# p2_eth_rs232.net
KiCad netlist of a schematic drawn in Altium Designer
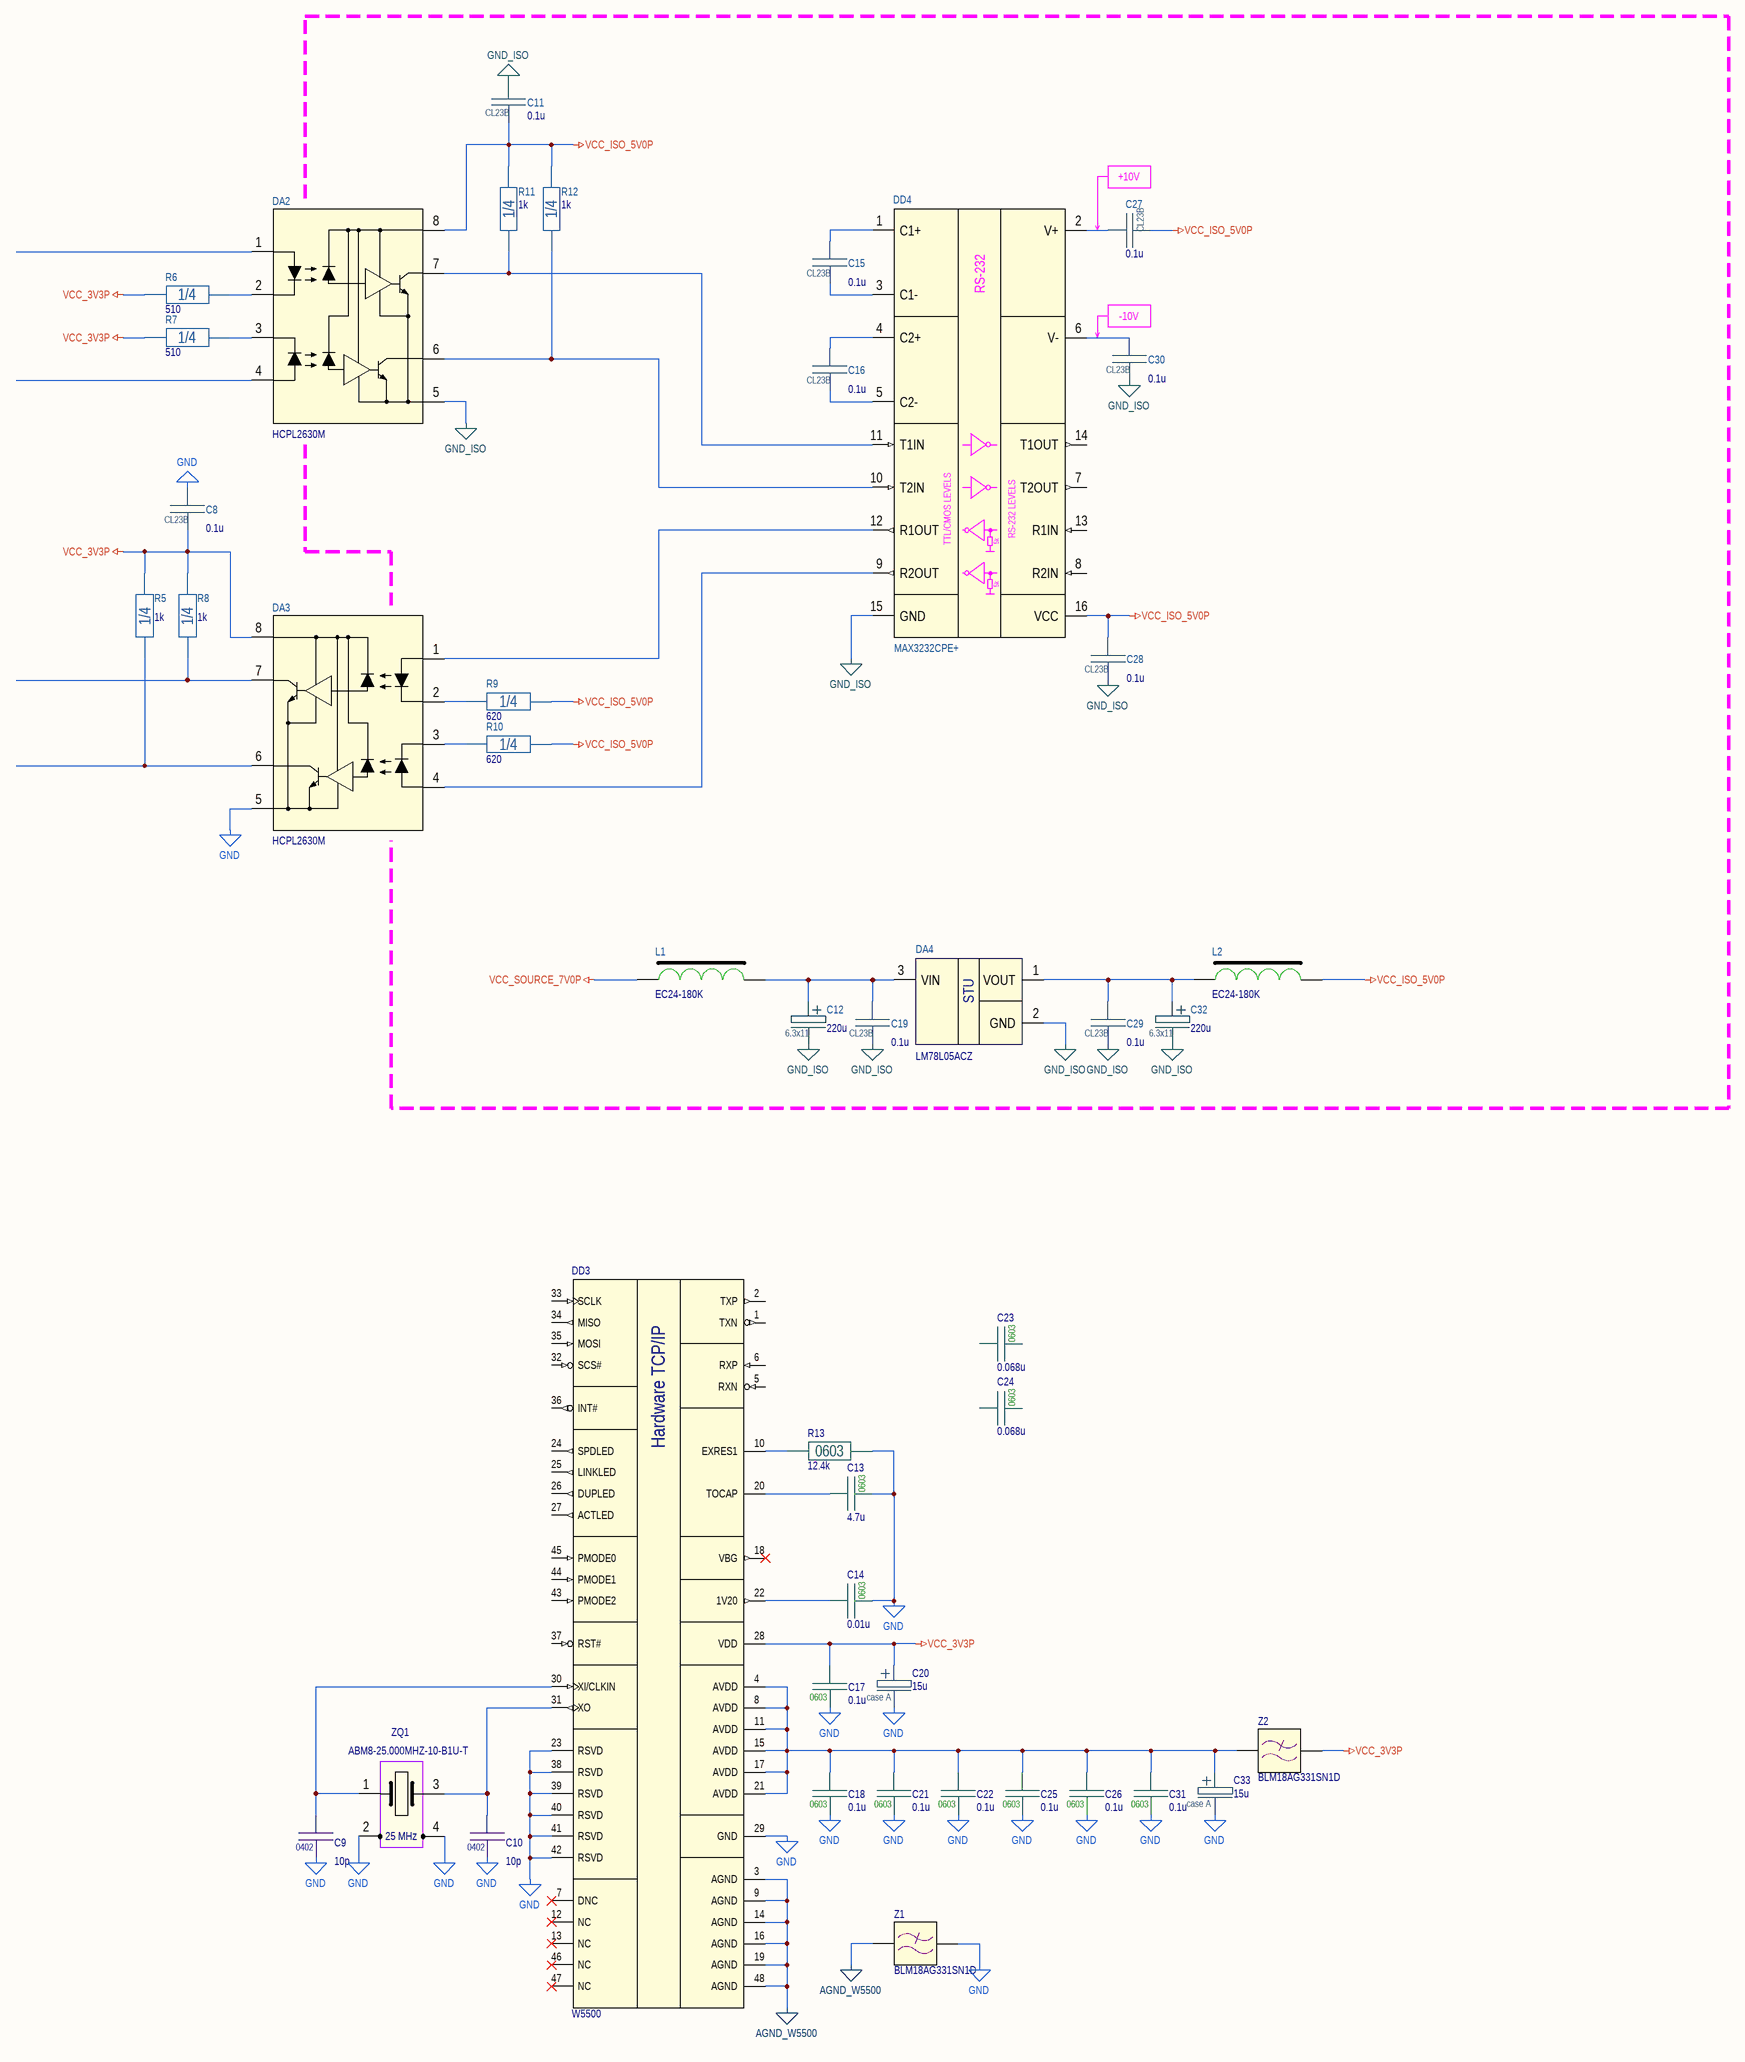
[diagram p0: p2_eth_rs232.SchDoc]

(export (version "E")
  (design (tool "Eeschema 10.0.6"))
  (components
    (comp (ref "C8")
      (value "0.1u")
      (footprint "PcbLib_RC:CL23B_7.2x2.5")
      (description "Box-type metallized polyester film capacitor")
      (fields
        (field (name "TOLERANCE") "± * %")
        (field (name "VOLTAGE") "63V")
        (field (name "PACKAGE") "CL23B")
      )
      (libsource (lib "Schlib_RC") (part "CL23B"))
    )
    (comp (ref "C9")
      (value "10p")
      (footprint "PcbLib_RC:CAP0402")
      (description "Capacitors 0402 package case")
      (fields
        (field (name "TOLERANCE") "± 10 %")
        (field (name "VOLTAGE") "50 V")
        (field (name "PACKAGE") "0402")
      )
      (libsource (lib "Schlib_RC") (part "C0402"))
    )
    (comp (ref "C10")
      (value "10p")
      (footprint "PcbLib_RC:CAP0402")
      (description "Capacitors 0402 package case")
      (fields
        (field (name "TOLERANCE") "± 10 %")
        (field (name "VOLTAGE") "50 V")
        (field (name "PACKAGE") "0402")
      )
      (libsource (lib "Schlib_RC") (part "C0402"))
    )
    (comp (ref "C11")
      (value "0.1u")
      (footprint "PcbLib_RC:CL23B_7.2x2.5")
      (description "Box-type metallized polyester film capacitor")
      (fields
        (field (name "TOLERANCE") "± * %")
        (field (name "VOLTAGE") "63V")
        (field (name "PACKAGE") "CL23B")
      )
      (libsource (lib "Schlib_RC") (part "CL23B"))
    )
    (comp (ref "C12")
      (value "220u")
      (footprint "PcbLib_RC:ECAP6.3X11X2.5_BRW")
      (description "Aluminium capacitor")
      (fields
        (field (name "TOLERANCE") "± 20 %")
        (field (name "VOLTAGE") "16V")
        (field (name "PACKAGE") "6.3x11")
      )
      (libsource (lib "Schlib_RC") (part "C_ECAP"))
    )
    (comp (ref "C13")
      (value "4.7u")
      (footprint "PcbLib_RC:CAP0603")
      (description "Capacitors 0603 package case")
      (fields
        (field (name "TOLERANCE") "± 10 %")
        (field (name "VOLTAGE") "16 V")
        (field (name "PACKAGE") "0603")
      )
      (libsource (lib "Schlib_RC") (part "C0603"))
    )
    (comp (ref "C14")
      (value "0.01u")
      (footprint "PcbLib_RC:CAP0603")
      (description "Capacitors 0603 package case")
      (fields
        (field (name "TOLERANCE") "± 10 %")
        (field (name "VOLTAGE") "50 V")
        (field (name "PACKAGE") "0603")
      )
      (libsource (lib "Schlib_RC") (part "C0603"))
    )
    (comp (ref "C15")
      (value "0.1u")
      (footprint "PcbLib_RC:CL23B_7.2x2.5")
      (description "Box-type metallized polyester film capacitor")
      (fields
        (field (name "TOLERANCE") "± * %")
        (field (name "VOLTAGE") "63V")
        (field (name "PACKAGE") "CL23B")
      )
      (libsource (lib "Schlib_RC") (part "CL23B"))
    )
    (comp (ref "C16")
      (value "0.1u")
      (footprint "PcbLib_RC:CL23B_7.2x2.5")
      (description "Box-type metallized polyester film capacitor")
      (fields
        (field (name "TOLERANCE") "± * %")
        (field (name "VOLTAGE") "63V")
        (field (name "PACKAGE") "CL23B")
      )
      (libsource (lib "Schlib_RC") (part "CL23B"))
    )
    (comp (ref "C17")
      (value "0.1u")
      (footprint "PcbLib_RC:CAP0603")
      (description "Capacitors 0603 package case")
      (fields
        (field (name "TOLERANCE") "± 10 %")
        (field (name "VOLTAGE") "50V")
        (field (name "PACKAGE") "0603")
      )
      (libsource (lib "Schlib_RC") (part "C0603"))
    )
    (comp (ref "C18")
      (value "0.1u")
      (footprint "PcbLib_RC:CAP0603")
      (description "Capacitors 0603 package case")
      (fields
        (field (name "TOLERANCE") "± 10 %")
        (field (name "VOLTAGE") "50V")
        (field (name "PACKAGE") "0603")
      )
      (libsource (lib "Schlib_RC") (part "C0603"))
    )
    (comp (ref "C19")
      (value "0.1u")
      (footprint "PcbLib_RC:CL23B_7.2x2.5")
      (description "Box-type metallized polyester film capacitor")
      (fields
        (field (name "TOLERANCE") "± * %")
        (field (name "VOLTAGE") "63V")
        (field (name "PACKAGE") "CL23B")
      )
      (libsource (lib "Schlib_RC") (part "CL23B"))
    )
    (comp (ref "C20")
      (value "15u")
      (footprint "PcbLib_RC:CAP_CASE_A")
      (description "Tantalum capacitors case A")
      (fields
        (field (name "TOLERANCE") "± 10 %")
        (field (name "VOLTAGE") "6.3V")
        (field (name "PACKAGE") "case A")
      )
      (libsource (lib "Schlib_RC") (part "C_CASEA"))
    )
    (comp (ref "C21")
      (value "0.1u")
      (footprint "PcbLib_RC:CAP0603")
      (description "Capacitors 0603 package case")
      (fields
        (field (name "TOLERANCE") "± 10 %")
        (field (name "VOLTAGE") "50V")
        (field (name "PACKAGE") "0603")
      )
      (libsource (lib "Schlib_RC") (part "C0603"))
    )
    (comp (ref "C22")
      (value "0.1u")
      (footprint "PcbLib_RC:CAP0603")
      (description "Capacitors 0603 package case")
      (fields
        (field (name "TOLERANCE") "± 10 %")
        (field (name "VOLTAGE") "50V")
        (field (name "PACKAGE") "0603")
      )
      (libsource (lib "Schlib_RC") (part "C0603"))
    )
    (comp (ref "C23")
      (value "0.068u")
      (footprint "PcbLib_RC:CAP0603")
      (description "Capacitors 0603 package case")
      (fields
        (field (name "TOLERANCE") "± 10 %")
        (field (name "VOLTAGE") "50 V")
        (field (name "PACKAGE") "0603")
      )
      (libsource (lib "Schlib_RC") (part "C0603"))
    )
    (comp (ref "C24")
      (value "0.068u")
      (footprint "PcbLib_RC:CAP0603")
      (description "Capacitors 0603 package case")
      (fields
        (field (name "TOLERANCE") "± 10 %")
        (field (name "VOLTAGE") "50 V")
        (field (name "PACKAGE") "0603")
      )
      (libsource (lib "Schlib_RC") (part "C0603"))
    )
    (comp (ref "C25")
      (value "0.1u")
      (footprint "PcbLib_RC:CAP0603")
      (description "Capacitors 0603 package case")
      (fields
        (field (name "TOLERANCE") "± 10 %")
        (field (name "VOLTAGE") "50V")
        (field (name "PACKAGE") "0603")
      )
      (libsource (lib "Schlib_RC") (part "C0603"))
    )
    (comp (ref "C26")
      (value "0.1u")
      (footprint "PcbLib_RC:CAP0603")
      (description "Capacitors 0603 package case")
      (fields
        (field (name "TOLERANCE") "± 10 %")
        (field (name "VOLTAGE") "50V")
        (field (name "PACKAGE") "0603")
      )
      (libsource (lib "Schlib_RC") (part "C0603"))
    )
    (comp (ref "C27")
      (value "0.1u")
      (footprint "PcbLib_RC:CL23B_7.2x2.5")
      (description "Box-type metallized polyester film capacitor")
      (fields
        (field (name "TOLERANCE") "± * %")
        (field (name "VOLTAGE") "63V")
        (field (name "PACKAGE") "CL23B")
      )
      (libsource (lib "Schlib_RC") (part "CL23B"))
    )
    (comp (ref "C28")
      (value "0.1u")
      (footprint "PcbLib_RC:CL23B_7.2x2.5")
      (description "Box-type metallized polyester film capacitor")
      (fields
        (field (name "TOLERANCE") "± * %")
        (field (name "VOLTAGE") "63V")
        (field (name "PACKAGE") "CL23B")
      )
      (libsource (lib "Schlib_RC") (part "CL23B"))
    )
    (comp (ref "C29")
      (value "0.1u")
      (footprint "PcbLib_RC:CL23B_7.2x2.5")
      (description "Box-type metallized polyester film capacitor")
      (fields
        (field (name "TOLERANCE") "± * %")
        (field (name "VOLTAGE") "63V")
        (field (name "PACKAGE") "CL23B")
      )
      (libsource (lib "Schlib_RC") (part "CL23B"))
    )
    (comp (ref "C30")
      (value "0.1u")
      (footprint "PcbLib_RC:CL23B_7.2x2.5")
      (description "Box-type metallized polyester film capacitor")
      (fields
        (field (name "TOLERANCE") "± * %")
        (field (name "VOLTAGE") "63V")
        (field (name "PACKAGE") "CL23B")
      )
      (libsource (lib "Schlib_RC") (part "CL23B"))
    )
    (comp (ref "C31")
      (value "0.1u")
      (footprint "PcbLib_RC:CAP0603")
      (description "Capacitors 0603 package case")
      (fields
        (field (name "TOLERANCE") "± 10 %")
        (field (name "VOLTAGE") "50V")
        (field (name "PACKAGE") "0603")
      )
      (libsource (lib "Schlib_RC") (part "C0603"))
    )
    (comp (ref "C32")
      (value "220u")
      (footprint "PcbLib_RC:ECAP6.3X11X2.5_BRW")
      (description "Aluminium capacitor")
      (fields
        (field (name "TOLERANCE") "± 20 %")
        (field (name "VOLTAGE") "16V")
        (field (name "PACKAGE") "6.3x11")
      )
      (libsource (lib "Schlib_RC") (part "C_ECAP"))
    )
    (comp (ref "C33")
      (value "15u")
      (footprint "PcbLib_RC:CAP_CASE_A")
      (description "Tantalum capacitors case A")
      (fields
        (field (name "TOLERANCE") "± 10 %")
        (field (name "VOLTAGE") "6.3V")
        (field (name "PACKAGE") "case A")
      )
      (libsource (lib "Schlib_RC") (part "C_CASEA"))
    )
    (comp (ref "DA2")
      (value "HCPL2630M")
      (footprint "PcbLib_ICs:DIP-8P-M01")
      (description "Dual-Channel High-Speed 10 MBit/s Logic Gate Optocouplers")
      (fields (field (name "MANUFACTURER") "ON Semiconductor"))
      (libsource (lib "Schlib_ONSemiconductor") (part "HCPL2630M"))
    )
    (comp (ref "DA3")
      (value "HCPL2630M")
      (footprint "PcbLib_ICs:DIP-8P-M01")
      (description "Dual-Channel High-Speed 10 MBit/s Logic Gate Optocouplers")
      (fields (field (name "MANUFACTURER") "ON Semiconductor"))
      (libsource (lib "Schlib_ONSemiconductor") (part "HCPL2630M"))
    )
    (comp (ref "DA4")
      (value "LM78L05ACZ")
      (footprint "PcbLib_ICs:TO-92 (VERTICAL,LINE)")
      (description "100-mA Fixed Output Linear Regulator")
      (fields (field (name "MANUFACTURER") "Texas Instruments"))
      (libsource (lib "Schlib_Texas_Instruments") (part "LM78L05ACZ"))
    )
    (comp (ref "DD3")
      (value "W5500")
      (footprint "PcbLib_ICs:LQFP-48")
      (description "Hardwired TCP/IP embedded Ethernet controller")
      (fields (field (name "MANUFACTURER") "WIZnet"))
      (libsource (lib "Schlib_Wiznet") (part "W5500"))
    )
    (comp (ref "DD4")
      (value "MAX3232CPE+")
      (footprint "PcbLib_ICs:DIP-16P-M03")
      (description "3.0V to 5.5V, Low-Power, Up to 1Mbps, True RS-232 Transceivers")
      (fields (field (name "MANUFACTURER") "Maxim Integrated"))
      (libsource (lib "Schlib_Maxim_Integrated") (part "MAX3232CPE+"))
    )
    (comp (ref "L1")
      (value "EC24-180K")
      (footprint "PcbLib_RC:EC24_GREEN")
      (description "Axial leaded coated inductors")
      (fields (field (name "MANUFACTURER") "3L Electronic"))
      (libsource (lib "Schlib_RC") (part "EC24"))
    )
    (comp (ref "L2")
      (value "EC24-180K")
      (footprint "PcbLib_RC:EC24_GREEN")
      (description "Axial leaded coated inductors")
      (fields (field (name "MANUFACTURER") "3L Electronic"))
      (libsource (lib "Schlib_RC") (part "EC24"))
    )
    (comp (ref "R5")
      (value "1k")
      (footprint "PcbLib_RC:CFR-25")
      (description "Resistor 1/4W")
      (fields
        (field (name "TOLERANCE") "± 1 %")
        (field (name "PART NUMBER") "MFR-25FTF52-1K")
        (field (name "PACKAGE") "1/4")
      )
      (libsource (lib "Schlib_RC") (part "CF25"))
    )
    (comp (ref "R6")
      (value "510")
      (footprint "PcbLib_RC:CFR-25")
      (description "Resistor 1/4W")
      (fields
        (field (name "TOLERANCE") "± 1 %")
        (field (name "PART NUMBER") "MFR-25FTF52-510R")
        (field (name "PACKAGE") "1/4")
      )
      (libsource (lib "Schlib_RC") (part "CF25"))
    )
    (comp (ref "R7")
      (value "510")
      (footprint "PcbLib_RC:CFR-25")
      (description "Resistor 1/4W")
      (fields
        (field (name "TOLERANCE") "± 1 %")
        (field (name "PART NUMBER") "MFR-25FTF52-510R")
        (field (name "PACKAGE") "1/4")
      )
      (libsource (lib "Schlib_RC") (part "CF25"))
    )
    (comp (ref "R8")
      (value "1k")
      (footprint "PcbLib_RC:CFR-25")
      (description "Resistor 1/4W")
      (fields
        (field (name "TOLERANCE") "± 1 %")
        (field (name "PART NUMBER") "MFR-25FTF52-1K")
        (field (name "PACKAGE") "1/4")
      )
      (libsource (lib "Schlib_RC") (part "CF25"))
    )
    (comp (ref "R9")
      (value "620")
      (footprint "PcbLib_RC:CFR-25")
      (description "Resistor 1/4W")
      (fields
        (field (name "TOLERANCE") "± 1 %")
        (field (name "PART NUMBER") "MFR-25FTF52-620R")
        (field (name "PACKAGE") "1/4")
      )
      (libsource (lib "Schlib_RC") (part "CF25"))
    )
    (comp (ref "R10")
      (value "620")
      (footprint "PcbLib_RC:CFR-25")
      (description "Resistor 1/4W")
      (fields
        (field (name "TOLERANCE") "± 1 %")
        (field (name "PART NUMBER") "MFR-25FTF52-620R")
        (field (name "PACKAGE") "1/4")
      )
      (libsource (lib "Schlib_RC") (part "CF25"))
    )
    (comp (ref "R11")
      (value "1k")
      (footprint "PcbLib_RC:CFR-25")
      (description "Resistor 1/4W")
      (fields
        (field (name "TOLERANCE") "± 1 %")
        (field (name "PART NUMBER") "MFR-25FTF52-1K")
        (field (name "PACKAGE") "1/4")
      )
      (libsource (lib "Schlib_RC") (part "CF25"))
    )
    (comp (ref "R12")
      (value "1k")
      (footprint "PcbLib_RC:CFR-25")
      (description "Resistor 1/4W")
      (fields
        (field (name "TOLERANCE") "± 1 %")
        (field (name "PART NUMBER") "MFR-25FTF52-1K")
        (field (name "PACKAGE") "1/4")
      )
      (libsource (lib "Schlib_RC") (part "CF25"))
    )
    (comp (ref "R13")
      (value "12.4k")
      (footprint "PcbLib_RC:RES0603B")
      (description "Resistor 0603 package case")
      (fields
        (field (name "TOLERANCE") "± 1 %")
        (field (name "PART NUMBER") "RC0603FR-0712K4L")
        (field (name "PACKAGE") "0603")
      )
      (libsource (lib "Schlib_RC") (part "R0603"))
    )
    (comp (ref "Z1")
      (value "BLM18AG331SN1D")
      (footprint "PcbLib_RC:BLM0603P")
      (description "Power line filter, imperdance 330 Ohm (current 05A)")
      (libsource (lib "Schlib_Murata") (part "BLM18AG331SN1D"))
    )
    (comp (ref "Z2")
      (value "BLM18AG331SN1D")
      (footprint "PcbLib_RC:BLM0603P")
      (description "Power line filter, imperdance 330 Ohm (current 05A)")
      (libsource (lib "Schlib_Murata") (part "BLM18AG331SN1D"))
    )
    (comp (ref "ZQ1")
      (value "ABM8-25.000MHZ-10-B1U-T")
      (footprint "PcbLib_Others:SMD3225")
      (description "Quartz Crystal (Frequency Stability ±10ppm)")
      (fields (field (name "MANUFACTURER") "Abracon LLC"))
      (libsource (lib "Schlib_AbraconLLC") (part "ABM8-25.000MHZ-10-B1U-T"))
    )
  )
  (nets
    (net (code "1") (name "AGND_W5500") (class "Default")
      (node (ref "DD3") (pin "14") (pinfunction "AGND_14") (pintype "power_in"))
      (node (ref "DD3") (pin "16") (pinfunction "AGND_16") (pintype "power_in"))
      (node (ref "DD3") (pin "19") (pinfunction "AGND_19") (pintype "power_in"))
      (node (ref "DD3") (pin "3") (pinfunction "AGND_3") (pintype "power_in"))
      (node (ref "DD3") (pin "48") (pinfunction "AGND_48") (pintype "power_in"))
      (node (ref "DD3") (pin "9") (pinfunction "AGND_9") (pintype "power_in"))
      (node (ref "Z1") (pin "2") (pinfunction "2_2") (pintype "passive"))
    )
    (net (code "2") (name "GND") (class "Default")
      (node (ref "C10") (pin "1") (pinfunction "1_1") (pintype "passive"))
      (node (ref "C13") (pin "2") (pinfunction "2_2") (pintype "passive"))
      (node (ref "C14") (pin "2") (pinfunction "2_2") (pintype "passive"))
      (node (ref "C17") (pin "1") (pinfunction "1_1") (pintype "passive"))
      (node (ref "C18") (pin "1") (pinfunction "1_1") (pintype "passive"))
      (node (ref "C20") (pin "2") (pinfunction "2_2") (pintype "passive"))
      (node (ref "C21") (pin "1") (pinfunction "1_1") (pintype "passive"))
      (node (ref "C22") (pin "1") (pinfunction "1_1") (pintype "passive"))
      (node (ref "C25") (pin "1") (pinfunction "1_1") (pintype "passive"))
      (node (ref "C26") (pin "1") (pinfunction "1_1") (pintype "passive"))
      (node (ref "C31") (pin "1") (pinfunction "1_1") (pintype "passive"))
      (node (ref "C33") (pin "2") (pinfunction "2_2") (pintype "passive"))
      (node (ref "C8") (pin "1") (pinfunction "1_1") (pintype "passive"))
      (node (ref "C9") (pin "1") (pinfunction "1_1") (pintype "passive"))
      (node (ref "DA3") (pin "5") (pinfunction "GND_5") (pintype "passive"))
      (node (ref "DD3") (pin "23") (pinfunction "RSVD_23") (pintype "tri_state"))
      (node (ref "DD3") (pin "29") (pinfunction "GND_29") (pintype "power_in"))
      (node (ref "DD3") (pin "38") (pinfunction "RSVD_38") (pintype "tri_state"))
      (node (ref "DD3") (pin "39") (pinfunction "RSVD_39") (pintype "tri_state"))
      (node (ref "DD3") (pin "40") (pinfunction "RSVD_40") (pintype "tri_state"))
      (node (ref "DD3") (pin "41") (pinfunction "RSVD_41") (pintype "tri_state"))
      (node (ref "DD3") (pin "42") (pinfunction "RSVD_42") (pintype "tri_state"))
      (node (ref "R13") (pin "2") (pinfunction "2_2") (pintype "passive"))
      (node (ref "Z1") (pin "1") (pinfunction "1_1") (pintype "passive"))
      (node (ref "ZQ1") (pin "2") (pinfunction "GND_2") (pintype "power_in"))
      (node (ref "ZQ1") (pin "4") (pinfunction "GND_4") (pintype "power_in"))
    )
    (net (code "3") (name "GND_ISO") (class "Default")
      (node (ref "C11") (pin "1") (pinfunction "1_1") (pintype "passive"))
      (node (ref "C12") (pin "2") (pinfunction "2_2") (pintype "passive"))
      (node (ref "C19") (pin "2") (pinfunction "2_2") (pintype "passive"))
      (node (ref "C28") (pin "2") (pinfunction "2_2") (pintype "passive"))
      (node (ref "C29") (pin "2") (pinfunction "2_2") (pintype "passive"))
      (node (ref "C30") (pin "2") (pinfunction "2_2") (pintype "passive"))
      (node (ref "C32") (pin "2") (pinfunction "2_2") (pintype "passive"))
      (node (ref "DA2") (pin "5") (pinfunction "GND_5") (pintype "passive"))
      (node (ref "DA4") (pin "2") (pinfunction "GND_2") (pintype "power_in"))
      (node (ref "DD4") (pin "15") (pinfunction "GND_15") (pintype "power_in"))
    )
    (net (code "4") (name "Net-(C18-Pad2)") (class "Default")
      (node (ref "C18") (pin "2") (pinfunction "2_2") (pintype "passive"))
      (node (ref "C21") (pin "2") (pinfunction "2_2") (pintype "passive"))
      (node (ref "C22") (pin "2") (pinfunction "2_2") (pintype "passive"))
      (node (ref "C25") (pin "2") (pinfunction "2_2") (pintype "passive"))
      (node (ref "C26") (pin "2") (pinfunction "2_2") (pintype "passive"))
      (node (ref "C31") (pin "2") (pinfunction "2_2") (pintype "passive"))
      (node (ref "C33") (pin "1") (pinfunction "1_1") (pintype "passive"))
      (node (ref "DD3") (pin "11") (pinfunction "AVDD_11") (pintype "power_in"))
      (node (ref "DD3") (pin "15") (pinfunction "AVDD_15") (pintype "power_in"))
      (node (ref "DD3") (pin "17") (pinfunction "AVDD_17") (pintype "power_in"))
      (node (ref "DD3") (pin "21") (pinfunction "AVDD_21") (pintype "power_in"))
      (node (ref "DD3") (pin "4") (pinfunction "AVDD_4") (pintype "power_in"))
      (node (ref "DD3") (pin "8") (pinfunction "AVDD_8") (pintype "power_in"))
      (node (ref "Z2") (pin "2") (pinfunction "2_2") (pintype "passive"))
    )
    (net (code "5") (name "Net-(DA2-CATHODE1)") (class "Default")
      (node (ref "DA2") (pin "2") (pinfunction "CATHODE1_2") (pintype "power_in"))
      (node (ref "R6") (pin "2") (pinfunction "2_2") (pintype "passive"))
    )
    (net (code "6") (name "Net-(DA2-CATHODE2)") (class "Default")
      (node (ref "DA2") (pin "3") (pinfunction "CATHODE2_3") (pintype "power_in"))
      (node (ref "R7") (pin "2") (pinfunction "2_2") (pintype "passive"))
    )
    (net (code "7") (name "Net-(DA2-V01)") (class "Default")
      (node (ref "DA2") (pin "7") (pinfunction "V01_7") (pintype "passive"))
      (node (ref "DD4") (pin "11") (pinfunction "T1IN_11") (pintype "input"))
      (node (ref "R11") (pin "2") (pinfunction "2_2") (pintype "passive"))
    )
    (net (code "8") (name "Net-(DA2-V02)") (class "Default")
      (node (ref "DA2") (pin "6") (pinfunction "V02_6") (pintype "passive"))
      (node (ref "DD4") (pin "10") (pinfunction "T2IN_10") (pintype "input"))
      (node (ref "R12") (pin "2") (pinfunction "2_2") (pintype "passive"))
    )
    (net (code "9") (name "Net-(DA3-ANODE1)") (class "Default")
      (node (ref "DA3") (pin "1") (pinfunction "ANODE1_1") (pintype "passive"))
      (node (ref "DD4") (pin "12") (pinfunction "R1OUT_12") (pintype "output"))
    )
    (net (code "10") (name "Net-(DA3-ANODE2)") (class "Default")
      (node (ref "DA3") (pin "4") (pinfunction "ANODE2_4") (pintype "passive"))
      (node (ref "DD4") (pin "9") (pinfunction "R2OUT_9") (pintype "output"))
    )
    (net (code "11") (name "Net-(DA3-CATHODE1)") (class "Default")
      (node (ref "DA3") (pin "2") (pinfunction "CATHODE1_2") (pintype "power_in"))
      (node (ref "R9") (pin "2") (pinfunction "2_2") (pintype "passive"))
    )
    (net (code "12") (name "Net-(DA3-CATHODE2)") (class "Default")
      (node (ref "DA3") (pin "3") (pinfunction "CATHODE2_3") (pintype "power_in"))
      (node (ref "R10") (pin "2") (pinfunction "2_2") (pintype "passive"))
    )
    (net (code "13") (name "Net-(DA3-V01)") (class "Default")
      (node (ref "DA3") (pin "7") (pinfunction "V01_7") (pintype "passive"))
      (node (ref "R8") (pin "2") (pinfunction "2_2") (pintype "passive"))
    )
    (net (code "14") (name "Net-(DA3-V02)") (class "Default")
      (node (ref "DA3") (pin "6") (pinfunction "V02_6") (pintype "passive"))
      (node (ref "R5") (pin "2") (pinfunction "2_2") (pintype "passive"))
    )
    (net (code "15") (name "Net-(DA4-VIN)") (class "Default")
      (node (ref "C12") (pin "1") (pinfunction "1_1") (pintype "passive"))
      (node (ref "C19") (pin "1") (pinfunction "1_1") (pintype "passive"))
      (node (ref "DA4") (pin "3") (pinfunction "VIN_3") (pintype "power_in"))
      (node (ref "L1") (pin "2") (pinfunction "2_2") (pintype "passive"))
    )
    (net (code "16") (name "Net-(DA4-VOUT)") (class "Default")
      (node (ref "C29") (pin "1") (pinfunction "1_1") (pintype "passive"))
      (node (ref "C32") (pin "1") (pinfunction "1_1") (pintype "passive"))
      (node (ref "DA4") (pin "1") (pinfunction "VOUT_1") (pintype "power_in"))
      (node (ref "L2") (pin "1") (pinfunction "1_1") (pintype "passive"))
    )
    (net (code "17") (name "Net-(DD3-1V20)") (class "Default")
      (node (ref "C14") (pin "1") (pinfunction "1_1") (pintype "passive"))
      (node (ref "DD3") (pin "22") (pinfunction "1V20_22") (pintype "output"))
    )
    (net (code "18") (name "Net-(DD3-EXRES1)") (class "Default")
      (node (ref "DD3") (pin "10") (pinfunction "EXRES1_10") (pintype "passive"))
      (node (ref "R13") (pin "1") (pinfunction "1_1") (pintype "passive"))
    )
    (net (code "19") (name "Net-(DD3-TOCAP)") (class "Default")
      (node (ref "C13") (pin "1") (pinfunction "1_1") (pintype "passive"))
      (node (ref "DD3") (pin "20") (pinfunction "TOCAP_20") (pintype "passive"))
    )
    (net (code "20") (name "Net-(DD3-XI{slash}CLKIN)") (class "Default")
      (node (ref "C9") (pin "2") (pinfunction "2_2") (pintype "passive"))
      (node (ref "DD3") (pin "30") (pinfunction "XI/CLKIN_30") (pintype "input"))
      (node (ref "ZQ1") (pin "1") (pinfunction "XTAL0_1") (pintype "passive"))
    )
    (net (code "21") (name "Net-(DD3-XO)") (class "Default")
      (node (ref "C10") (pin "2") (pinfunction "2_2") (pintype "passive"))
      (node (ref "DD3") (pin "31") (pinfunction "XO_31") (pintype "output"))
      (node (ref "ZQ1") (pin "3") (pinfunction "XTAL1_3") (pintype "passive"))
    )
    (net (code "22") (name "Net-(DD4-C1+)") (class "Default")
      (node (ref "C15") (pin "1") (pinfunction "1_1") (pintype "passive"))
      (node (ref "DD4") (pin "1") (pinfunction "C1+_1") (pintype "passive"))
    )
    (net (code "23") (name "Net-(DD4-C1-)") (class "Default")
      (node (ref "C15") (pin "2") (pinfunction "2_2") (pintype "passive"))
      (node (ref "DD4") (pin "3") (pinfunction "C1-_3") (pintype "passive"))
    )
    (net (code "24") (name "Net-(DD4-C2+)") (class "Default")
      (node (ref "C16") (pin "1") (pinfunction "1_1") (pintype "passive"))
      (node (ref "DD4") (pin "4") (pinfunction "C2+_4") (pintype "passive"))
    )
    (net (code "25") (name "Net-(DD4-C2-)") (class "Default")
      (node (ref "C16") (pin "2") (pinfunction "2_2") (pintype "passive"))
      (node (ref "DD4") (pin "5") (pinfunction "C2-_5") (pintype "passive"))
    )
    (net (code "26") (name "Net-(DD4-V+)") (class "Default")
      (node (ref "C27") (pin "1") (pinfunction "1_1") (pintype "passive"))
      (node (ref "DD4") (pin "2") (pinfunction "V+_2") (pintype "passive"))
    )
    (net (code "27") (name "Net-(DD4-V-)") (class "Default")
      (node (ref "C30") (pin "1") (pinfunction "1_1") (pintype "passive"))
      (node (ref "DD4") (pin "6") (pinfunction "V-_6") (pintype "passive"))
    )
    (net (code "28") (name "VCC_3V3P") (class "Default")
      (node (ref "C17") (pin "2") (pinfunction "2_2") (pintype "passive"))
      (node (ref "C20") (pin "1") (pinfunction "1_1") (pintype "passive"))
      (node (ref "C8") (pin "2") (pinfunction "2_2") (pintype "passive"))
      (node (ref "DA3") (pin "8") (pinfunction "VCC_8") (pintype "power_in"))
      (node (ref "DD3") (pin "28") (pinfunction "VDD_28") (pintype "power_in"))
      (node (ref "R5") (pin "1") (pinfunction "1_1") (pintype "passive"))
      (node (ref "R6") (pin "1") (pinfunction "1_1") (pintype "passive"))
      (node (ref "R7") (pin "1") (pinfunction "1_1") (pintype "passive"))
      (node (ref "R8") (pin "1") (pinfunction "1_1") (pintype "passive"))
      (node (ref "Z2") (pin "1") (pinfunction "1_1") (pintype "passive"))
    )
    (net (code "29") (name "VCC_ISO_5V0P") (class "Default")
      (node (ref "C11") (pin "2") (pinfunction "2_2") (pintype "passive"))
      (node (ref "C27") (pin "2") (pinfunction "2_2") (pintype "passive"))
      (node (ref "C28") (pin "1") (pinfunction "1_1") (pintype "passive"))
      (node (ref "DA2") (pin "8") (pinfunction "VCC_8") (pintype "power_in"))
      (node (ref "DD4") (pin "16") (pinfunction "VCC_16") (pintype "power_in"))
      (node (ref "L2") (pin "2") (pinfunction "2_2") (pintype "passive"))
      (node (ref "R10") (pin "1") (pinfunction "1_1") (pintype "passive"))
      (node (ref "R11") (pin "1") (pinfunction "1_1") (pintype "passive"))
      (node (ref "R12") (pin "1") (pinfunction "1_1") (pintype "passive"))
      (node (ref "R9") (pin "1") (pinfunction "1_1") (pintype "passive"))
    )
    (net (code "30") (name "VCC_SOURCE_7V0P") (class "Default")
      (node (ref "L1") (pin "1") (pinfunction "1_1") (pintype "passive"))
    )
    (net (code "31") (name "unconnected-(C23-Pad1)") (class "Default")
      (node (ref "C23") (pin "1") (pinfunction "1_1") (pintype "passive"))
    )
    (net (code "32") (name "unconnected-(C23-Pad2)") (class "Default")
      (node (ref "C23") (pin "2") (pinfunction "2_2") (pintype "passive"))
    )
    (net (code "33") (name "unconnected-(C24-Pad1)") (class "Default")
      (node (ref "C24") (pin "1") (pinfunction "1_1") (pintype "passive"))
    )
    (net (code "34") (name "unconnected-(C24-Pad2)") (class "Default")
      (node (ref "C24") (pin "2") (pinfunction "2_2") (pintype "passive"))
    )
    (net (code "35") (name "unconnected-(DA2-ANODE1-Pad1)") (class "Default")
      (node (ref "DA2") (pin "1") (pinfunction "ANODE1_1") (pintype "passive"))
    )
    (net (code "36") (name "unconnected-(DA2-ANODE2-Pad4)") (class "Default")
      (node (ref "DA2") (pin "4") (pinfunction "ANODE2_4") (pintype "passive"))
    )
    (net (code "37") (name "unconnected-(DD3-ACTLED-Pad27)") (class "Default")
      (node (ref "DD3") (pin "27") (pinfunction "ACTLED_27") (pintype "output"))
    )
    (net (code "38") (name "unconnected-(DD3-DNC-Pad7)") (class "Default")
      (node (ref "DD3") (pin "7") (pinfunction "DNC_7") (pintype "tri_state+no_connect"))
    )
    (net (code "39") (name "unconnected-(DD3-DUPLED-Pad26)") (class "Default")
      (node (ref "DD3") (pin "26") (pinfunction "DUPLED_26") (pintype "output"))
    )
    (net (code "40") (name "unconnected-(DD3-INT#-Pad36)") (class "Default")
      (node (ref "DD3") (pin "36") (pinfunction "INT#_36") (pintype "output"))
    )
    (net (code "41") (name "unconnected-(DD3-LINKLED-Pad25)") (class "Default")
      (node (ref "DD3") (pin "25") (pinfunction "LINKLED_25") (pintype "output"))
    )
    (net (code "42") (name "unconnected-(DD3-MISO-Pad34)") (class "Default")
      (node (ref "DD3") (pin "34") (pinfunction "MISO_34") (pintype "output"))
    )
    (net (code "43") (name "unconnected-(DD3-MOSI-Pad35)") (class "Default")
      (node (ref "DD3") (pin "35") (pinfunction "MOSI_35") (pintype "input"))
    )
    (net (code "44") (name "unconnected-(DD3-NC-Pad12)") (class "Default")
      (node (ref "DD3") (pin "12") (pinfunction "NC_12") (pintype "tri_state+no_connect"))
    )
    (net (code "45") (name "unconnected-(DD3-NC-Pad13)") (class "Default")
      (node (ref "DD3") (pin "13") (pinfunction "NC_13") (pintype "tri_state+no_connect"))
    )
    (net (code "46") (name "unconnected-(DD3-NC-Pad46)") (class "Default")
      (node (ref "DD3") (pin "46") (pinfunction "NC_46") (pintype "tri_state+no_connect"))
    )
    (net (code "47") (name "unconnected-(DD3-NC-Pad47)") (class "Default")
      (node (ref "DD3") (pin "47") (pinfunction "NC_47") (pintype "tri_state+no_connect"))
    )
    (net (code "48") (name "unconnected-(DD3-PMODE0-Pad45)") (class "Default")
      (node (ref "DD3") (pin "45") (pinfunction "PMODE0_45") (pintype "input"))
    )
    (net (code "49") (name "unconnected-(DD3-PMODE1-Pad44)") (class "Default")
      (node (ref "DD3") (pin "44") (pinfunction "PMODE1_44") (pintype "input"))
    )
    (net (code "50") (name "unconnected-(DD3-PMODE2-Pad43)") (class "Default")
      (node (ref "DD3") (pin "43") (pinfunction "PMODE2_43") (pintype "input"))
    )
    (net (code "51") (name "unconnected-(DD3-RST#-Pad37)") (class "Default")
      (node (ref "DD3") (pin "37") (pinfunction "RST#_37") (pintype "input"))
    )
    (net (code "52") (name "unconnected-(DD3-RXN-Pad5)") (class "Default")
      (node (ref "DD3") (pin "5") (pinfunction "RXN_5") (pintype "input"))
    )
    (net (code "53") (name "unconnected-(DD3-RXP-Pad6)") (class "Default")
      (node (ref "DD3") (pin "6") (pinfunction "RXP_6") (pintype "input"))
    )
    (net (code "54") (name "unconnected-(DD3-SCLK-Pad33)") (class "Default")
      (node (ref "DD3") (pin "33") (pinfunction "SCLK_33") (pintype "input"))
    )
    (net (code "55") (name "unconnected-(DD3-SCS#-Pad32)") (class "Default")
      (node (ref "DD3") (pin "32") (pinfunction "SCS#_32") (pintype "input"))
    )
    (net (code "56") (name "unconnected-(DD3-SPDLED-Pad24)") (class "Default")
      (node (ref "DD3") (pin "24") (pinfunction "SPDLED_24") (pintype "output"))
    )
    (net (code "57") (name "unconnected-(DD3-TXN-Pad1)") (class "Default")
      (node (ref "DD3") (pin "1") (pinfunction "TXN_1") (pintype "output"))
    )
    (net (code "58") (name "unconnected-(DD3-TXP-Pad2)") (class "Default")
      (node (ref "DD3") (pin "2") (pinfunction "TXP_2") (pintype "output"))
    )
    (net (code "59") (name "unconnected-(DD3-VBG-Pad18)") (class "Default")
      (node (ref "DD3") (pin "18") (pinfunction "VBG_18") (pintype "output+no_connect"))
    )
    (net (code "60") (name "unconnected-(DD4-R1IN-Pad13)") (class "Default")
      (node (ref "DD4") (pin "13") (pinfunction "R1IN_13") (pintype "input"))
    )
    (net (code "61") (name "unconnected-(DD4-R2IN-Pad8)") (class "Default")
      (node (ref "DD4") (pin "8") (pinfunction "R2IN_8") (pintype "input"))
    )
    (net (code "62") (name "unconnected-(DD4-T1OUT-Pad14)") (class "Default")
      (node (ref "DD4") (pin "14") (pinfunction "T1OUT_14") (pintype "output"))
    )
    (net (code "63") (name "unconnected-(DD4-T2OUT-Pad7)") (class "Default")
      (node (ref "DD4") (pin "7") (pinfunction "T2OUT_7") (pintype "output"))
    )
  )
)
